# ECT_RADIATOR_FAN_CIRCUIT_for_Launchpad.net
KiCad netlist of a schematic drawn in EAGLE
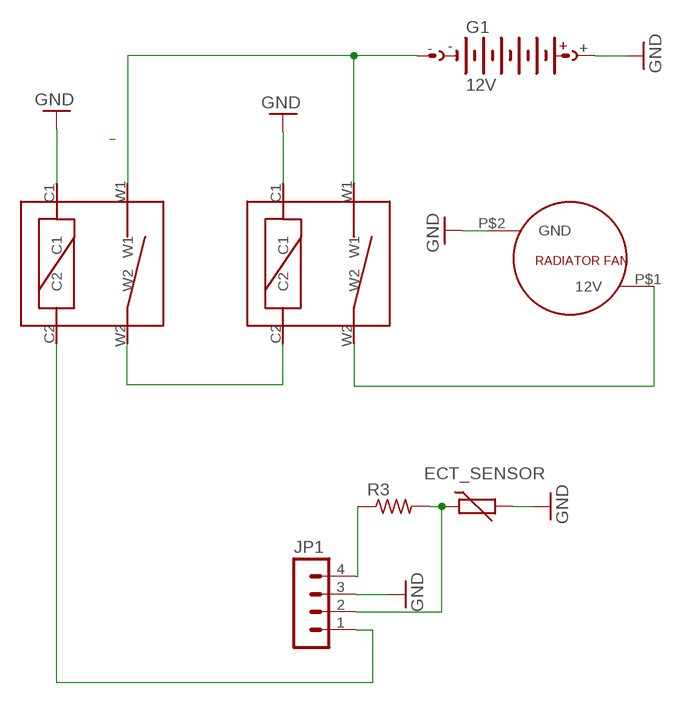
[diagram p0: schematic, sheet 1]

(export (version "E")
  (design (tool "Eeschema 10.0.6"))
  (components
    (comp (ref "3.3V,10A")
      (value "3.3V, 10A")
      (footprint "eagle-import:RELAY_AUTO")
      (libsource (lib "eagle-import") (part "RELAY_AUTO"))
    )
    (comp (ref "12V,30A")
      (value "12V, 30A")
      (footprint "eagle-import:RELAY_AUTO")
      (libsource (lib "eagle-import") (part "RELAY_AUTO"))
    )
    (comp (ref "ECT_SENSOR")
      (value "THERMISTOR-5")
      (footprint "eagle-import:R-5")
      (libsource (lib "eagle-import") (part "THERMISTOR-5"))
    )
    (comp (ref "G1")
      (value "12V")
      (footprint "eagle-import:AB9V")
      (libsource (lib "eagle-import") (part "AB9V"))
    )
    (comp (ref "JP1")
      (value "MA04-1")
      (footprint "eagle-import:MA04-1")
      (libsource (lib "eagle-import") (part "MA04-1"))
    )
    (comp (ref "R3")
      (value "R-US_0207/7")
      (footprint "eagle-import:0207_7")
      (libsource (lib "eagle-import") (part "R-US_0207/7"))
    )
    (comp (ref "U$4")
      (value "FAN")
      (footprint "eagle-import:FAN")
      (libsource (lib "eagle-import") (part "FAN"))
    )
  )
  (nets
    (net (code "1") (name "GND") (class "Default")
      (node (ref "12V,30A") (pin "C1") (pinfunction "C1_C1") (pintype "bidirectional"))
      (node (ref "3.3V,10A") (pin "C1") (pinfunction "C1_C1") (pintype "bidirectional"))
      (node (ref "ECT_SENSOR") (pin "2") (pinfunction "2_2") (pintype "passive"))
      (node (ref "G1") (pin "+") (pinfunction "+_+") (pintype "passive"))
      (node (ref "JP1") (pin "3") (pinfunction "3_3") (pintype "passive"))
      (node (ref "U$4") (pin "P$2") (pinfunction "GND_P$2") (pintype "bidirectional"))
    )
    (net (code "2") (name "Net-(3.3V,10A-PadC2)") (class "Default")
      (node (ref "3.3V,10A") (pin "C2") (pinfunction "C2_C2") (pintype "bidirectional"))
      (node (ref "JP1") (pin "1") (pinfunction "1_1") (pintype "passive"))
    )
    (net (code "3") (name "Net-(12V,30A-PadC2)") (class "Default")
      (node (ref "12V,30A") (pin "C2") (pinfunction "C2_C2") (pintype "bidirectional"))
      (node (ref "3.3V,10A") (pin "W2") (pinfunction "W2_W2") (pintype "bidirectional"))
    )
    (net (code "4") (name "Net-(12V,30A-PadW1)") (class "Default")
      (node (ref "12V,30A") (pin "W1") (pinfunction "W1_W1") (pintype "bidirectional"))
      (node (ref "3.3V,10A") (pin "W1") (pinfunction "W1_W1") (pintype "bidirectional"))
      (node (ref "G1") (pin "-") (pinfunction "-_-") (pintype "passive"))
    )
    (net (code "5") (name "Net-(ECT_SENSOR-Pad1)") (class "Default")
      (node (ref "ECT_SENSOR") (pin "1") (pinfunction "1_1") (pintype "passive"))
      (node (ref "JP1") (pin "2") (pinfunction "2_2") (pintype "passive"))
      (node (ref "R3") (pin "2") (pinfunction "2_2") (pintype "passive"))
    )
    (net (code "6") (name "Net-(JP1-Pad4)") (class "Default")
      (node (ref "JP1") (pin "4") (pinfunction "4_4") (pintype "passive"))
      (node (ref "R3") (pin "1") (pinfunction "1_1") (pintype "passive"))
    )
    (net (code "7") (name "Net-(U$4-12V)") (class "Default")
      (node (ref "12V,30A") (pin "W2") (pinfunction "W2_W2") (pintype "bidirectional"))
      (node (ref "U$4") (pin "P$1") (pinfunction "12V_P$1") (pintype "bidirectional"))
    )
  )
)
